# untitled.net
KiCad netlist of a schematic drawn in EAGLE
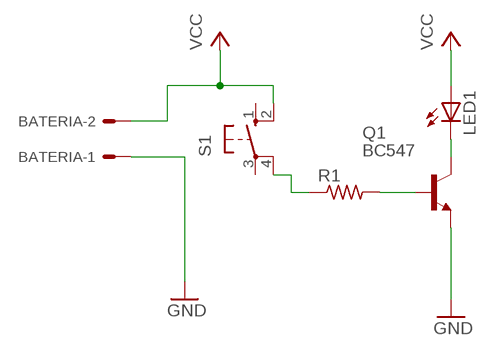
[diagram p0: schematic, sheet 1]

(export (version "E")
  (design (tool "Eeschema 10.0.6"))
  (components
    (comp (ref "BATERIA")
      (value "KK-156-2")
      (footprint "eagle-import:KK-156-2")
      (fields (field (name "MF") "MOLEX"))
      (libsource (lib "eagle-import") (part "KK-156-2"))
    )
    (comp (ref "LED1")
      (value "LED5MM")
      (footprint "eagle-import:LED5MM")
      (libsource (lib "eagle-import") (part "LED5MM"))
    )
    (comp (ref "Q1")
      (value "BC547")
      (footprint "eagle-import:TO92")
      (libsource (lib "eagle-import") (part "BC547"))
    )
    (comp (ref "R1")
      (value "R-US_0207/7")
      (footprint "eagle-import:0207_7")
      (libsource (lib "eagle-import") (part "R-US_0207/7"))
    )
    (comp (ref "S1")
      (value "10-XX")
      (footprint "eagle-import:B3F-10XX")
      (fields (field (name "MPN") "B3F-1000"))
      (libsource (lib "eagle-import") (part "10-XX"))
    )
  )
  (nets
    (net (code "1") (name "GND") (class "Default")
      (node (ref "BATERIA") (pin "1") (pinfunction "S_1") (pintype "passive"))
      (node (ref "Q1") (pin "1") (pinfunction "E_1") (pintype "passive"))
    )
    (net (code "2") (name "Net-(LED1-C)") (class "Default")
      (node (ref "LED1") (pin "K") (pinfunction "C_K") (pintype "passive"))
      (node (ref "Q1") (pin "3") (pinfunction "C_3") (pintype "passive"))
    )
    (net (code "3") (name "Net-(Q1-B)") (class "Default")
      (node (ref "Q1") (pin "2") (pinfunction "B_2") (pintype "passive"))
      (node (ref "R1") (pin "2") (pinfunction "2_2") (pintype "passive"))
    )
    (net (code "4") (name "Net-(S1-P1)") (class "Default")
      (node (ref "R1") (pin "1") (pinfunction "1_1") (pintype "passive"))
      (node (ref "S1") (pin "4") (pinfunction "P1_4") (pintype "passive"))
    )
    (net (code "5") (name "VCC") (class "Default")
      (node (ref "BATERIA") (pin "2") (pinfunction "S_2") (pintype "passive"))
      (node (ref "LED1") (pin "A") (pinfunction "A_A") (pintype "passive"))
      (node (ref "S1") (pin "2") (pinfunction "S1_2") (pintype "passive"))
    )
    (net (code "6") (name "unconnected-(S1-P-Pad3)") (class "Default")
      (node (ref "S1") (pin "3") (pinfunction "P_3") (pintype "passive"))
    )
    (net (code "7") (name "unconnected-(S1-S-Pad1)") (class "Default")
      (node (ref "S1") (pin "1") (pinfunction "S_1") (pintype "passive"))
    )
  )
)
